# Schematic.net
KiCad netlist of a schematic drawn in EAGLE
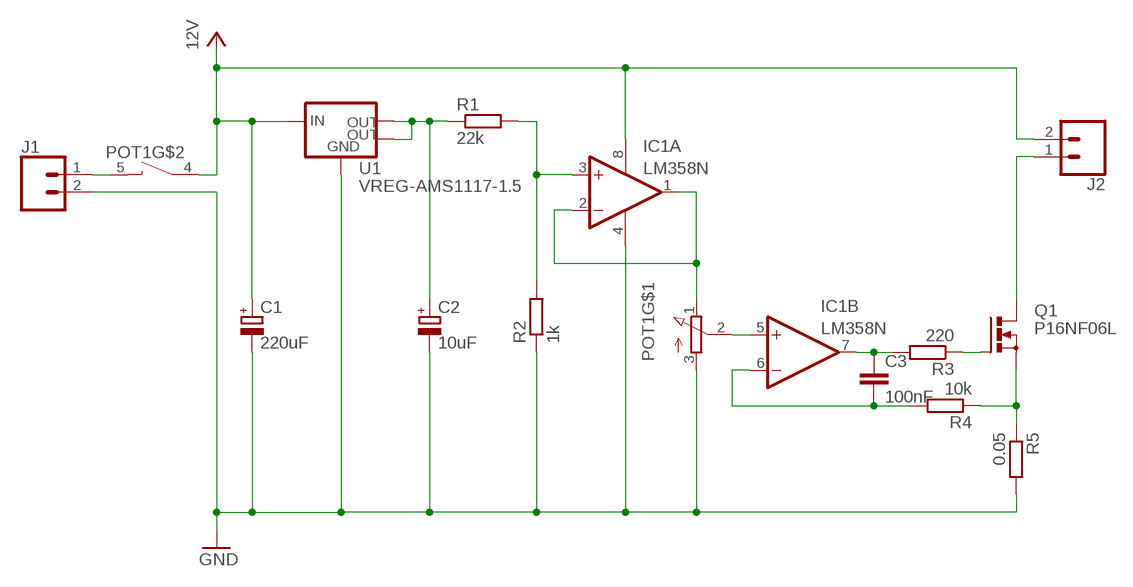
[diagram p0: schematic, sheet 1]

(export (version "E")
  (design (tool "Eeschema 10.0.6"))
  (components
    (comp (ref "C1")
      (value "220uF")
      (footprint "eagle-import:PANASONIC_F")
      (libsource (lib "eagle-import") (part "CPOL-EUF"))
    )
    (comp (ref "C2")
      (value "10uF")
      (footprint "eagle-import:PANASONIC_B")
      (libsource (lib "eagle-import") (part "CPOL-EUB"))
    )
    (comp (ref "C3")
      (value "100nF")
      (footprint "eagle-import:C025-025X050")
      (libsource (lib "eagle-import") (part "C-EU025-025X050"))
    )
    (comp (ref "IC1")
      (value "LM358N")
      (footprint "eagle-import:DIL08")
      (libsource (lib "eagle-import") (part "LM358N"))
    )
    (comp (ref "J1")
      (value "SCREW-TERM")
      (footprint "eagle-import:1X02_NO_SILK")
      (libsource (lib "eagle-import") (part "SCREW-TERM"))
    )
    (comp (ref "J2")
      (value "SCREW-TERM")
      (footprint "eagle-import:1X02_NO_SILK")
      (libsource (lib "eagle-import") (part "SCREW-TERM"))
    )
    (comp (ref "POT1")
      (value "POT-SWITCH")
      (footprint "eagle-import:POT-SWITCH-PTH")
      (libsource (lib "eagle-import") (part "POT-SWITCH"))
    )
    (comp (ref "Q1")
      (value "P16NF06L")
      (footprint "eagle-import:TO220BV")
      (libsource (lib "eagle-import") (part "PMOSFET_NTO220BV"))
    )
    (comp (ref "R1")
      (value "22k")
      (footprint "eagle-import:R1206")
      (libsource (lib "eagle-import") (part "R-EU_R1206"))
    )
    (comp (ref "R2")
      (value "1k")
      (footprint "eagle-import:R1206")
      (libsource (lib "eagle-import") (part "R-EU_R1206"))
    )
    (comp (ref "R3")
      (value "220")
      (footprint "eagle-import:R1206")
      (libsource (lib "eagle-import") (part "R-EU_R1206"))
    )
    (comp (ref "R4")
      (value "10k")
      (footprint "eagle-import:R1206")
      (libsource (lib "eagle-import") (part "R-EU_R1206"))
    )
    (comp (ref "R5")
      (value "0.05")
      (footprint "eagle-import:R2512")
      (libsource (lib "eagle-import") (part "R-EU_R2512"))
    )
    (comp (ref "U1")
      (value "VREG-AMS1117-1.5")
      (footprint "eagle-import:SOT230P700X180-4")
      (libsource (lib "eagle-import") (part "VREG-AMS1117-1.5"))
    )
  )
  (nets
    (net (code "1") (name "12V") (class "Default")
      (node (ref "C1") (pin "+") (pinfunction "+_+") (pintype "passive"))
      (node (ref "IC1") (pin "8") (pinfunction "V+_8") (pintype "power_in"))
      (node (ref "J2") (pin "2") (pinfunction "1_2") (pintype "passive"))
      (node (ref "POT1") (pin "4") (pinfunction "P$1_4") (pintype "bidirectional"))
      (node (ref "U1") (pin "3") (pinfunction "IN_3") (pintype "input"))
    )
    (net (code "2") (name "GND") (class "Default")
      (node (ref "C1") (pin "-") (pinfunction "-_-") (pintype "passive"))
      (node (ref "C2") (pin "-") (pinfunction "-_-") (pintype "passive"))
      (node (ref "IC1") (pin "4") (pinfunction "V-_4") (pintype "power_in"))
      (node (ref "J1") (pin "2") (pinfunction "1_2") (pintype "passive"))
      (node (ref "POT1") (pin "3") (pinfunction "P$3_3") (pintype "bidirectional"))
      (node (ref "R2") (pin "1") (pinfunction "1_1") (pintype "passive"))
      (node (ref "R5") (pin "2") (pinfunction "2_2") (pintype "passive"))
      (node (ref "U1") (pin "1") (pinfunction "GND_1") (pintype "input"))
    )
    (net (code "3") (name "Net-(C2-Pad+)") (class "Default")
      (node (ref "C2") (pin "+") (pinfunction "+_+") (pintype "passive"))
      (node (ref "R1") (pin "1") (pinfunction "1_1") (pintype "passive"))
      (node (ref "U1") (pin "2") (pinfunction "OUT_2") (pintype "output"))
      (node (ref "U1") (pin "4") (pinfunction "OUT_4") (pintype "output"))
    )
    (net (code "4") (name "Net-(IC1A-+IN)") (class "Default")
      (node (ref "IC1") (pin "3") (pinfunction "+IN_3") (pintype "input"))
      (node (ref "R1") (pin "2") (pinfunction "2_2") (pintype "passive"))
      (node (ref "R2") (pin "2") (pinfunction "2_2") (pintype "passive"))
    )
    (net (code "5") (name "Net-(IC1A--IN)") (class "Default")
      (node (ref "IC1") (pin "1") (pinfunction "OUT_1") (pintype "output"))
      (node (ref "IC1") (pin "2") (pinfunction "-IN_2") (pintype "input"))
      (node (ref "POT1") (pin "1") (pinfunction "P$1_1") (pintype "bidirectional"))
    )
    (net (code "6") (name "Net-(IC1B-+IN)") (class "Default")
      (node (ref "IC1") (pin "5") (pinfunction "+IN_5") (pintype "input"))
      (node (ref "POT1") (pin "2") (pinfunction "P$2_2") (pintype "bidirectional"))
    )
    (net (code "7") (name "Net-(IC1B--IN)") (class "Default")
      (node (ref "C3") (pin "2") (pinfunction "2_2") (pintype "passive"))
      (node (ref "IC1") (pin "6") (pinfunction "-IN_6") (pintype "input"))
      (node (ref "R4") (pin "2") (pinfunction "2_2") (pintype "passive"))
    )
    (net (code "8") (name "Net-(IC1B-OUT)") (class "Default")
      (node (ref "C3") (pin "1") (pinfunction "1_1") (pintype "passive"))
      (node (ref "IC1") (pin "7") (pinfunction "OUT_7") (pintype "output"))
      (node (ref "R3") (pin "2") (pinfunction "2_2") (pintype "passive"))
    )
    (net (code "9") (name "Net-(J1-2)") (class "Default")
      (node (ref "J1") (pin "1") (pinfunction "2_1") (pintype "passive"))
      (node (ref "POT1") (pin "5") (pinfunction "P$2_5") (pintype "bidirectional"))
    )
    (net (code "10") (name "Net-(J2-2)") (class "Default")
      (node (ref "J2") (pin "1") (pinfunction "2_1") (pintype "passive"))
      (node (ref "Q1") (pin "D") (pinfunction "D_D") (pintype "passive"))
    )
    (net (code "11") (name "Net-(Q1-PadG)") (class "Default")
      (node (ref "Q1") (pin "G") (pinfunction "G_G") (pintype "passive"))
      (node (ref "R3") (pin "1") (pinfunction "1_1") (pintype "passive"))
    )
    (net (code "12") (name "Net-(Q1-PadS)") (class "Default")
      (node (ref "Q1") (pin "S") (pinfunction "S_S") (pintype "passive"))
      (node (ref "R4") (pin "1") (pinfunction "1_1") (pintype "passive"))
      (node (ref "R5") (pin "1") (pinfunction "1_1") (pintype "passive"))
    )
  )
)
